# PCB-CMB-5-ETHERMEGA.net
KiCad netlist of a schematic drawn in EAGLE
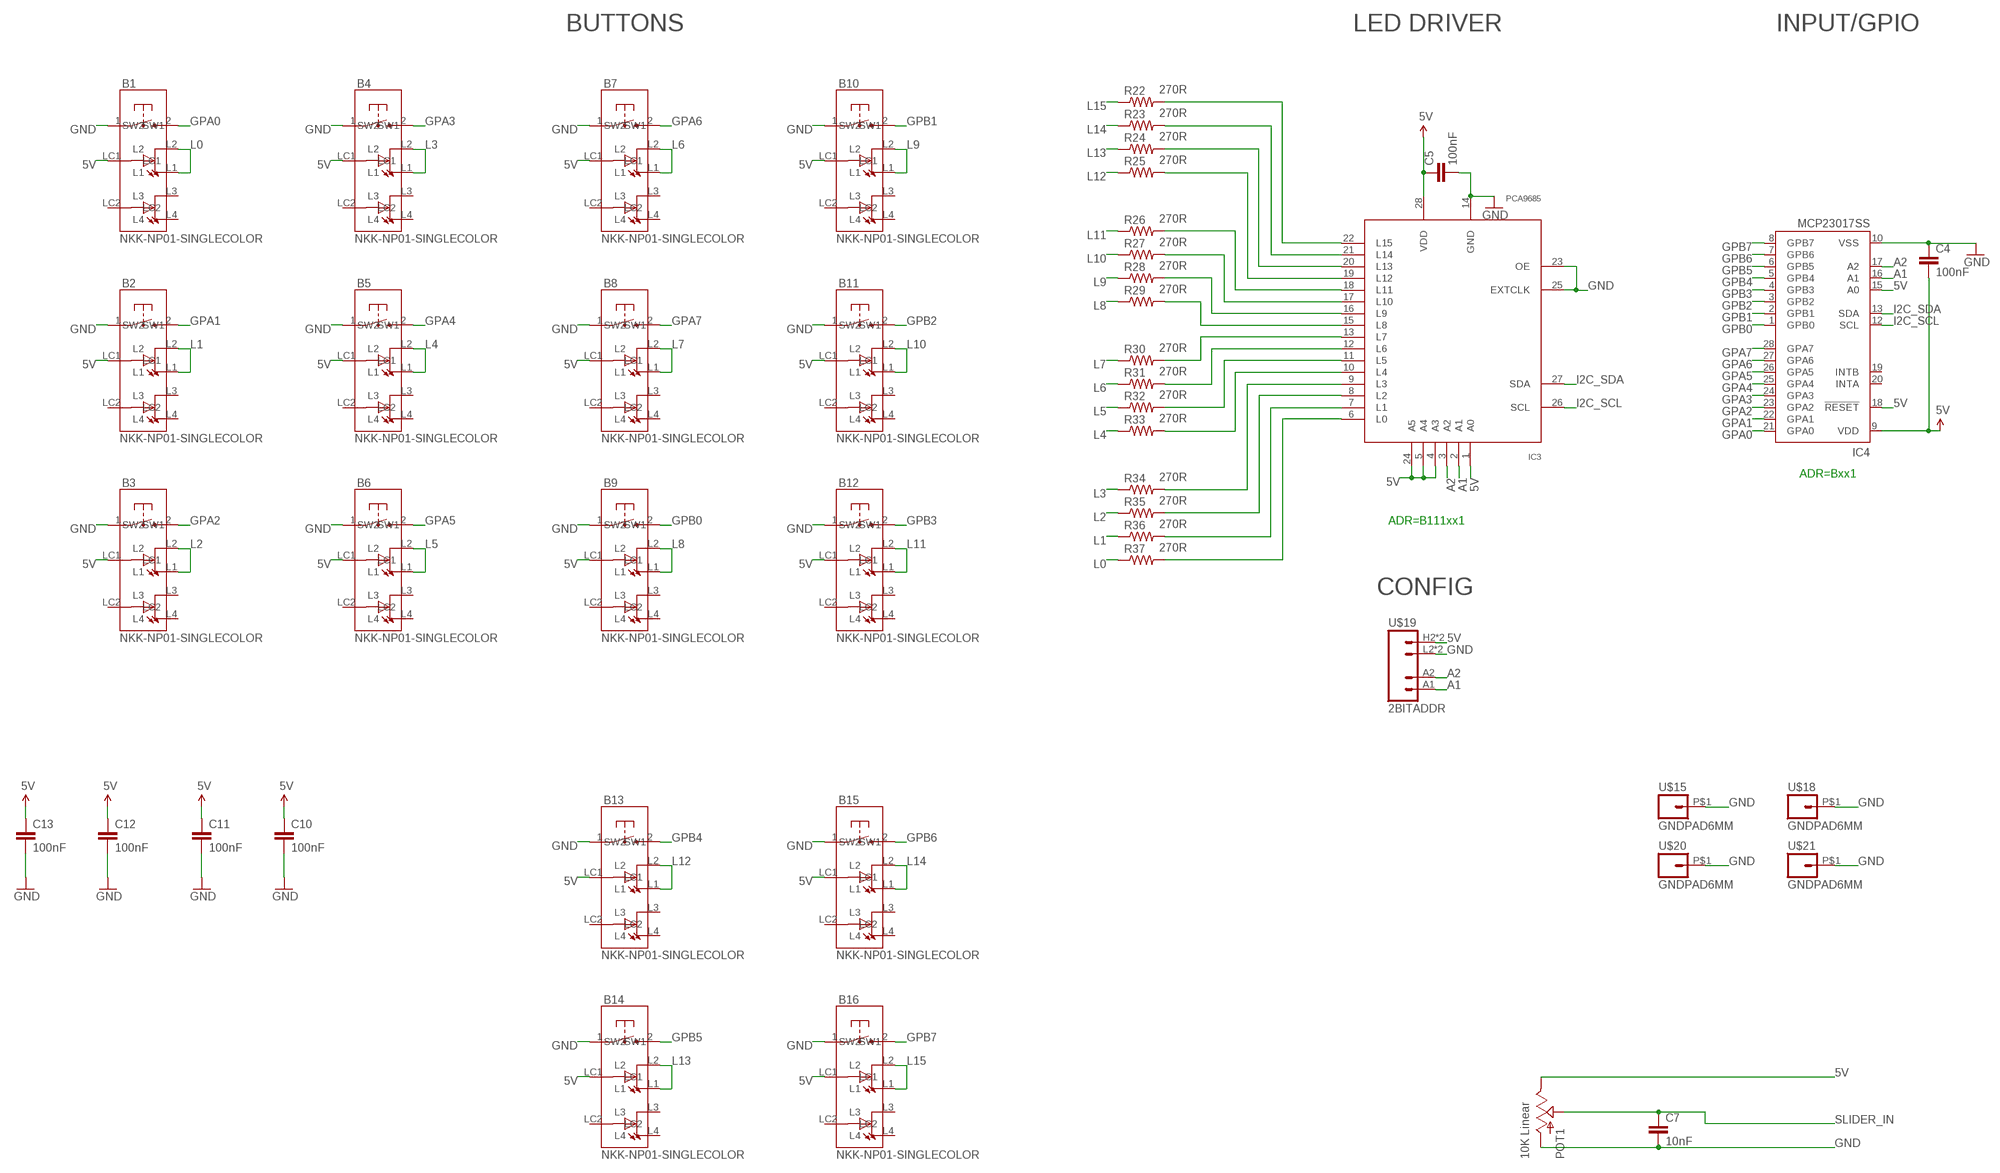
[diagram p0: schematic, sheet 1, part 1 of 2]
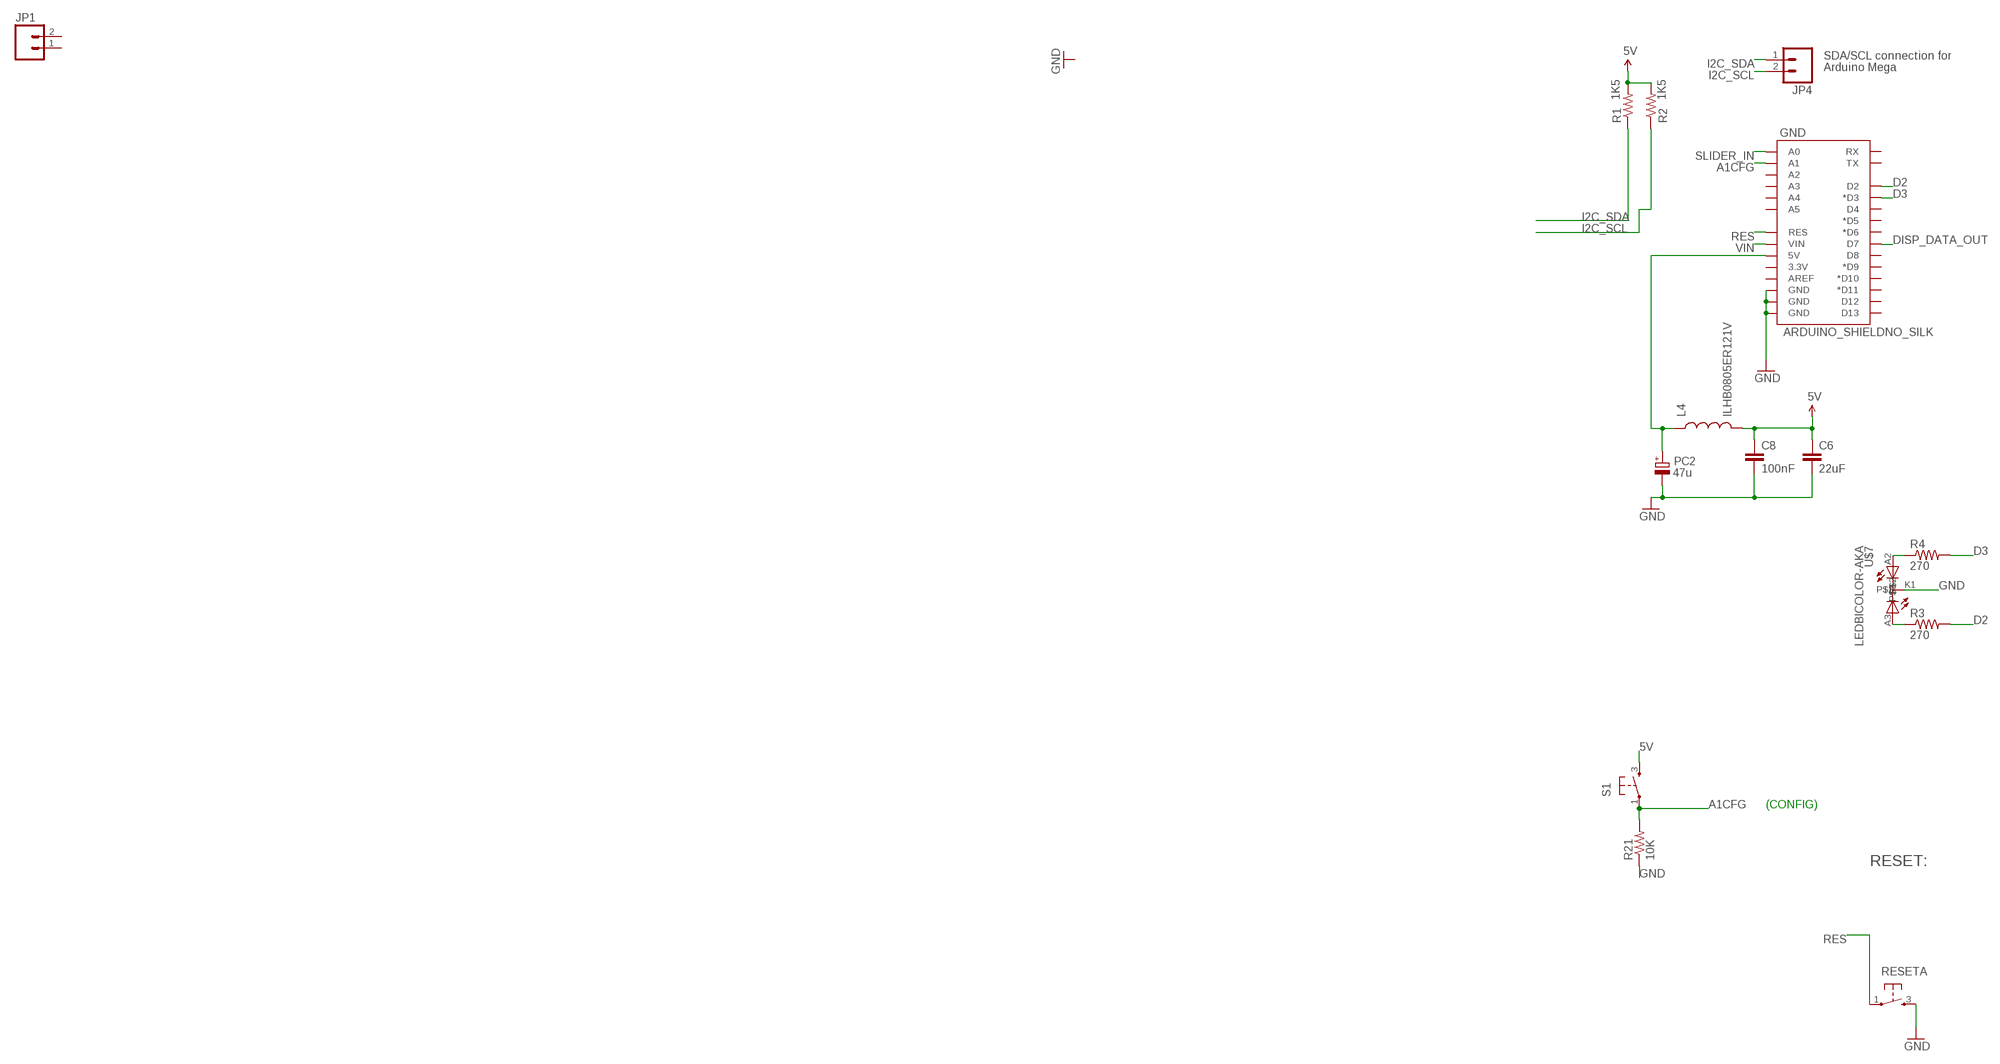
[diagram p1: schematic, sheet 1, part 2 of 2]

(export (version "E")
  (design (tool "Eeschema 10.0.6"))
  (components
    (comp (ref "B1")
      (value "NKK-NP01-SINGLECOLOR")
      (footprint "eagle-import:NKK-NP01")
      (libsource (lib "eagle-import") (part "NKK-NP01-SINGLECOLOR"))
    )
    (comp (ref "B2")
      (value "NKK-NP01-SINGLECOLOR")
      (footprint "eagle-import:NKK-NP01")
      (libsource (lib "eagle-import") (part "NKK-NP01-SINGLECOLOR"))
    )
    (comp (ref "B3")
      (value "NKK-NP01-SINGLECOLOR")
      (footprint "eagle-import:NKK-NP01")
      (libsource (lib "eagle-import") (part "NKK-NP01-SINGLECOLOR"))
    )
    (comp (ref "B4")
      (value "NKK-NP01-SINGLECOLOR")
      (footprint "eagle-import:NKK-NP01")
      (libsource (lib "eagle-import") (part "NKK-NP01-SINGLECOLOR"))
    )
    (comp (ref "B5")
      (value "NKK-NP01-SINGLECOLOR")
      (footprint "eagle-import:NKK-NP01")
      (libsource (lib "eagle-import") (part "NKK-NP01-SINGLECOLOR"))
    )
    (comp (ref "B6")
      (value "NKK-NP01-SINGLECOLOR")
      (footprint "eagle-import:NKK-NP01")
      (libsource (lib "eagle-import") (part "NKK-NP01-SINGLECOLOR"))
    )
    (comp (ref "B7")
      (value "NKK-NP01-SINGLECOLOR")
      (footprint "eagle-import:NKK-NP01")
      (libsource (lib "eagle-import") (part "NKK-NP01-SINGLECOLOR"))
    )
    (comp (ref "B8")
      (value "NKK-NP01-SINGLECOLOR")
      (footprint "eagle-import:NKK-NP01")
      (libsource (lib "eagle-import") (part "NKK-NP01-SINGLECOLOR"))
    )
    (comp (ref "B9")
      (value "NKK-NP01-SINGLECOLOR")
      (footprint "eagle-import:NKK-NP01")
      (libsource (lib "eagle-import") (part "NKK-NP01-SINGLECOLOR"))
    )
    (comp (ref "B10")
      (value "NKK-NP01-SINGLECOLOR")
      (footprint "eagle-import:NKK-NP01")
      (libsource (lib "eagle-import") (part "NKK-NP01-SINGLECOLOR"))
    )
    (comp (ref "B11")
      (value "NKK-NP01-SINGLECOLOR")
      (footprint "eagle-import:NKK-NP01")
      (libsource (lib "eagle-import") (part "NKK-NP01-SINGLECOLOR"))
    )
    (comp (ref "B12")
      (value "NKK-NP01-SINGLECOLOR")
      (footprint "eagle-import:NKK-NP01")
      (libsource (lib "eagle-import") (part "NKK-NP01-SINGLECOLOR"))
    )
    (comp (ref "B13")
      (value "NKK-NP01-SINGLECOLOR")
      (footprint "eagle-import:NKK-NP01")
      (libsource (lib "eagle-import") (part "NKK-NP01-SINGLECOLOR"))
    )
    (comp (ref "B14")
      (value "NKK-NP01-SINGLECOLOR")
      (footprint "eagle-import:NKK-NP01")
      (libsource (lib "eagle-import") (part "NKK-NP01-SINGLECOLOR"))
    )
    (comp (ref "B15")
      (value "NKK-NP01-SINGLECOLOR")
      (footprint "eagle-import:NKK-NP01")
      (libsource (lib "eagle-import") (part "NKK-NP01-SINGLECOLOR"))
    )
    (comp (ref "B16")
      (value "NKK-NP01-SINGLECOLOR")
      (footprint "eagle-import:NKK-NP01")
      (libsource (lib "eagle-import") (part "NKK-NP01-SINGLECOLOR"))
    )
    (comp (ref "C4")
      (value "100nF")
      (footprint "eagle-import:0603-CAP")
      (libsource (lib "eagle-import") (part "CAP0603-CAP"))
    )
    (comp (ref "C5")
      (value "100nF")
      (footprint "eagle-import:0603-CAP")
      (libsource (lib "eagle-import") (part "CAP0603-CAP"))
    )
    (comp (ref "C6")
      (value "22uF")
      (footprint "eagle-import:0805")
      (libsource (lib "eagle-import") (part "CAP0805"))
    )
    (comp (ref "C7")
      (value "10nF")
      (footprint "eagle-import:0603-CAP")
      (libsource (lib "eagle-import") (part "CAP0603-CAP"))
    )
    (comp (ref "C8")
      (value "100nF")
      (footprint "eagle-import:0603-CAP")
      (libsource (lib "eagle-import") (part "CAP0603-CAP"))
    )
    (comp (ref "C10")
      (value "100nF")
      (footprint "eagle-import:0603-CAP")
      (libsource (lib "eagle-import") (part "CAP0603-CAP"))
    )
    (comp (ref "C11")
      (value "100nF")
      (footprint "eagle-import:0603-CAP")
      (libsource (lib "eagle-import") (part "CAP0603-CAP"))
    )
    (comp (ref "C12")
      (value "100nF")
      (footprint "eagle-import:0603-CAP")
      (libsource (lib "eagle-import") (part "CAP0603-CAP"))
    )
    (comp (ref "C13")
      (value "100nF")
      (footprint "eagle-import:0603-CAP")
      (libsource (lib "eagle-import") (part "CAP0603-CAP"))
    )
    (comp (ref "GND")
      (value "ARDUINO_SHIELDNO_SILK")
      (footprint "eagle-import:DUEMILANOVE_VIAS")
      (libsource (lib "eagle-import") (part "ARDUINO_SHIELDNO_SILK"))
    )
    (comp (ref "IC3")
      (value "PCA9685")
      (footprint "eagle-import:TSSOP28")
      (libsource (lib "eagle-import") (part "PCA9685"))
    )
    (comp (ref "IC4")
      (value "MCP23017SS")
      (footprint "eagle-import:SSOP28")
      (fields
        (field (name "MF") "MICROCHIP")
        (field (name "MPN") "MCP23017-E/SS")
        (field (name "MPN_1") "MCP23017-E/SS")
        (field (name "OC_FARNELL") "1467674")
        (field (name "OC_NEWARK") "31K2960")
      )
      (libsource (lib "eagle-import") (part "MCP23017SS"))
    )
    (comp (ref "JP1")
      (value "M02PTH")
      (footprint "eagle-import:1X02")
      (libsource (lib "eagle-import") (part "M02PTH"))
    )
    (comp (ref "JP4")
      (value "M02PTH")
      (footprint "eagle-import:1X02")
      (libsource (lib "eagle-import") (part "M02PTH"))
    )
    (comp (ref "L4")
      (value "ILHB0805ER121V")
      (footprint "eagle-import:0805")
      (libsource (lib "eagle-import") (part "INDUCTOR0805"))
    )
    (comp (ref "PC2")
      (value "47u")
      (footprint "eagle-import:PANASONIC_D")
      (libsource (lib "eagle-import") (part "CPOL-EUD"))
    )
    (comp (ref "POT1")
      (value "10K Linear")
      (footprint "eagle-import:SLIDER20")
      (libsource (lib "eagle-import") (part "SLIDER20"))
    )
    (comp (ref "R1")
      (value "1K5")
      (footprint "eagle-import:0603-RES")
      (libsource (lib "eagle-import") (part "RESISTOR0603-RES"))
    )
    (comp (ref "R2")
      (value "1K5")
      (footprint "eagle-import:0603-RES")
      (libsource (lib "eagle-import") (part "RESISTOR0603-RES"))
    )
    (comp (ref "R3")
      (value "270")
      (footprint "eagle-import:0603-RES")
      (libsource (lib "eagle-import") (part "RESISTOR0603-RES"))
    )
    (comp (ref "R4")
      (value "270")
      (footprint "eagle-import:0603-RES")
      (libsource (lib "eagle-import") (part "RESISTOR0603-RES"))
    )
    (comp (ref "R21")
      (value "10K")
      (footprint "eagle-import:0603-RES")
      (libsource (lib "eagle-import") (part "RESISTOR0603-RES"))
    )
    (comp (ref "R22")
      (value "270R")
      (footprint "eagle-import:0603-RES")
      (libsource (lib "eagle-import") (part "RESISTOR0603-RES"))
    )
    (comp (ref "R23")
      (value "270R")
      (footprint "eagle-import:0603-RES")
      (libsource (lib "eagle-import") (part "RESISTOR0603-RES"))
    )
    (comp (ref "R24")
      (value "270R")
      (footprint "eagle-import:0603-RES")
      (libsource (lib "eagle-import") (part "RESISTOR0603-RES"))
    )
    (comp (ref "R25")
      (value "270R")
      (footprint "eagle-import:0603-RES")
      (libsource (lib "eagle-import") (part "RESISTOR0603-RES"))
    )
    (comp (ref "R26")
      (value "270R")
      (footprint "eagle-import:0603-RES")
      (libsource (lib "eagle-import") (part "RESISTOR0603-RES"))
    )
    (comp (ref "R27")
      (value "270R")
      (footprint "eagle-import:0603-RES")
      (libsource (lib "eagle-import") (part "RESISTOR0603-RES"))
    )
    (comp (ref "R28")
      (value "270R")
      (footprint "eagle-import:0603-RES")
      (libsource (lib "eagle-import") (part "RESISTOR0603-RES"))
    )
    (comp (ref "R29")
      (value "270R")
      (footprint "eagle-import:0603-RES")
      (libsource (lib "eagle-import") (part "RESISTOR0603-RES"))
    )
    (comp (ref "R30")
      (value "270R")
      (footprint "eagle-import:0603-RES")
      (libsource (lib "eagle-import") (part "RESISTOR0603-RES"))
    )
    (comp (ref "R31")
      (value "270R")
      (footprint "eagle-import:0603-RES")
      (libsource (lib "eagle-import") (part "RESISTOR0603-RES"))
    )
    (comp (ref "R32")
      (value "270R")
      (footprint "eagle-import:0603-RES")
      (libsource (lib "eagle-import") (part "RESISTOR0603-RES"))
    )
    (comp (ref "R33")
      (value "270R")
      (footprint "eagle-import:0603-RES")
      (libsource (lib "eagle-import") (part "RESISTOR0603-RES"))
    )
    (comp (ref "R34")
      (value "270R")
      (footprint "eagle-import:0603-RES")
      (libsource (lib "eagle-import") (part "RESISTOR0603-RES"))
    )
    (comp (ref "R35")
      (value "270R")
      (footprint "eagle-import:0603-RES")
      (libsource (lib "eagle-import") (part "RESISTOR0603-RES"))
    )
    (comp (ref "R36")
      (value "270R")
      (footprint "eagle-import:0603-RES")
      (libsource (lib "eagle-import") (part "RESISTOR0603-RES"))
    )
    (comp (ref "R37")
      (value "270R")
      (footprint "eagle-import:0603-RES")
      (libsource (lib "eagle-import") (part "RESISTOR0603-RES"))
    )
    (comp (ref "RESETA")
      (value "TAC_SWITCH")
      (footprint "eagle-import:PUSHBUTTON")
      (libsource (lib "eagle-import") (part "TAC_SWITCH"))
    )
    (comp (ref "S1")
      (value "TAC_SWITCH")
      (footprint "eagle-import:PUSHBUTTON")
      (libsource (lib "eagle-import") (part "TAC_SWITCH"))
    )
    (comp (ref "U$7")
      (value "LEDBICOLOR-AKA")
      (footprint "eagle-import:LED5MM-BICOLOR")
      (libsource (lib "eagle-import") (part "LEDBICOLOR-AKA"))
    )
    (comp (ref "U$15")
      (value "GNDPAD6MM")
      (footprint "eagle-import:3.2MMPAD6MM")
      (libsource (lib "eagle-import") (part "GNDPAD6MM"))
    )
    (comp (ref "U$18")
      (value "GNDPAD6MM")
      (footprint "eagle-import:3.2MMPAD6MM")
      (libsource (lib "eagle-import") (part "GNDPAD6MM"))
    )
    (comp (ref "U$19")
      (value "2BITADDR")
      (footprint "eagle-import:2BITADDR")
      (libsource (lib "eagle-import") (part "2BITADDR"))
    )
    (comp (ref "U$20")
      (value "GNDPAD6MM")
      (footprint "eagle-import:3.2MMPAD6MM")
      (libsource (lib "eagle-import") (part "GNDPAD6MM"))
    )
    (comp (ref "U$21")
      (value "GNDPAD6MM")
      (footprint "eagle-import:3.2MMPAD6MM")
      (libsource (lib "eagle-import") (part "GNDPAD6MM"))
    )
  )
  (nets
    (net (code "1") (name "5V") (class "Default")
      (node (ref "B1") (pin "LC1") (pinfunction "LC1_LC1") (pintype "bidirectional"))
      (node (ref "B10") (pin "LC1") (pinfunction "LC1_LC1") (pintype "bidirectional"))
      (node (ref "B11") (pin "LC1") (pinfunction "LC1_LC1") (pintype "bidirectional"))
      (node (ref "B12") (pin "LC1") (pinfunction "LC1_LC1") (pintype "bidirectional"))
      (node (ref "B13") (pin "LC1") (pinfunction "LC1_LC1") (pintype "bidirectional"))
      (node (ref "B14") (pin "LC1") (pinfunction "LC1_LC1") (pintype "bidirectional"))
      (node (ref "B15") (pin "LC1") (pinfunction "LC1_LC1") (pintype "bidirectional"))
      (node (ref "B16") (pin "LC1") (pinfunction "LC1_LC1") (pintype "bidirectional"))
      (node (ref "B2") (pin "LC1") (pinfunction "LC1_LC1") (pintype "bidirectional"))
      (node (ref "B3") (pin "LC1") (pinfunction "LC1_LC1") (pintype "bidirectional"))
      (node (ref "B4") (pin "LC1") (pinfunction "LC1_LC1") (pintype "bidirectional"))
      (node (ref "B5") (pin "LC1") (pinfunction "LC1_LC1") (pintype "bidirectional"))
      (node (ref "B6") (pin "LC1") (pinfunction "LC1_LC1") (pintype "bidirectional"))
      (node (ref "B7") (pin "LC1") (pinfunction "LC1_LC1") (pintype "bidirectional"))
      (node (ref "B8") (pin "LC1") (pinfunction "LC1_LC1") (pintype "bidirectional"))
      (node (ref "B9") (pin "LC1") (pinfunction "LC1_LC1") (pintype "bidirectional"))
      (node (ref "C10") (pin "1") (pinfunction "1_1") (pintype "passive"))
      (node (ref "C11") (pin "1") (pinfunction "1_1") (pintype "passive"))
      (node (ref "C12") (pin "1") (pinfunction "1_1") (pintype "passive"))
      (node (ref "C13") (pin "1") (pinfunction "1_1") (pintype "passive"))
      (node (ref "C4") (pin "2") (pinfunction "2_2") (pintype "passive"))
      (node (ref "C5") (pin "1") (pinfunction "1_1") (pintype "passive"))
      (node (ref "C6") (pin "1") (pinfunction "1_1") (pintype "passive"))
      (node (ref "C8") (pin "1") (pinfunction "1_1") (pintype "passive"))
      (node (ref "IC3") (pin "1") (pinfunction "A0_1") (pintype "input"))
      (node (ref "IC3") (pin "24") (pinfunction "A5_24") (pintype "input"))
      (node (ref "IC3") (pin "28") (pinfunction "VDD_28") (pintype "power_in"))
      (node (ref "IC3") (pin "4") (pinfunction "A3_4") (pintype "input"))
      (node (ref "IC3") (pin "5") (pinfunction "A4_5") (pintype "input"))
      (node (ref "IC4") (pin "15") (pinfunction "A0_15") (pintype "input"))
      (node (ref "IC4") (pin "18") (pinfunction "~{RESET}_18") (pintype "input"))
      (node (ref "IC4") (pin "9") (pinfunction "VDD_9") (pintype "power_in"))
      (node (ref "L4") (pin "2") (pinfunction "2_2") (pintype "passive"))
      (node (ref "POT1") (pin "1") (pinfunction "E_1") (pintype "passive"))
      (node (ref "R1") (pin "2") (pinfunction "2_2") (pintype "passive"))
      (node (ref "R2") (pin "2") (pinfunction "2_2") (pintype "passive"))
      (node (ref "S1") (pin "3") (pinfunction "3_3") (pintype "passive"))
      (node (ref "U$19") (pin "H2") (pinfunction "VCC_H2") (pintype "passive"))
      (node (ref "U$19") (pin "H3") (pinfunction "VCC_H3") (pintype "passive"))
    )
    (net (code "2") (name "A1") (class "Default")
      (node (ref "IC3") (pin "2") (pinfunction "A1_2") (pintype "input"))
      (node (ref "IC4") (pin "16") (pinfunction "A1_16") (pintype "input"))
      (node (ref "U$19") (pin "A1") (pinfunction "A1_A1") (pintype "passive"))
    )
    (net (code "3") (name "A1CFG") (class "Default")
      (node (ref "GND") (pin "A1") (pinfunction "A1_A1") (pintype "bidirectional"))
      (node (ref "R21") (pin "2") (pinfunction "2_2") (pintype "passive"))
      (node (ref "S1") (pin "1") (pinfunction "1_1") (pintype "passive"))
    )
    (net (code "4") (name "A2") (class "Default")
      (node (ref "IC3") (pin "3") (pinfunction "A2_3") (pintype "input"))
      (node (ref "IC4") (pin "17") (pinfunction "A2_17") (pintype "input"))
      (node (ref "U$19") (pin "A2") (pinfunction "A2_A2") (pintype "passive"))
    )
    (net (code "5") (name "D2") (class "Default")
      (node (ref "GND") (pin "D2") (pinfunction "D2_D2") (pintype "bidirectional"))
      (node (ref "R3") (pin "2") (pinfunction "2_2") (pintype "passive"))
    )
    (net (code "6") (name "D3") (class "Default")
      (node (ref "GND") (pin "D3") (pinfunction "*D3_D3") (pintype "bidirectional"))
      (node (ref "R4") (pin "2") (pinfunction "2_2") (pintype "passive"))
    )
    (net (code "7") (name "DISP_DATA_OUT") (class "Default")
      (node (ref "GND") (pin "D7") (pinfunction "D7_D7") (pintype "bidirectional"))
    )
    (net (code "8") (name "GND") (class "Default")
      (node (ref "B1") (pin "1") (pinfunction "SW1_1") (pintype "bidirectional"))
      (node (ref "B10") (pin "1") (pinfunction "SW1_1") (pintype "bidirectional"))
      (node (ref "B11") (pin "1") (pinfunction "SW1_1") (pintype "bidirectional"))
      (node (ref "B12") (pin "1") (pinfunction "SW1_1") (pintype "bidirectional"))
      (node (ref "B13") (pin "1") (pinfunction "SW1_1") (pintype "bidirectional"))
      (node (ref "B14") (pin "1") (pinfunction "SW1_1") (pintype "bidirectional"))
      (node (ref "B15") (pin "1") (pinfunction "SW1_1") (pintype "bidirectional"))
      (node (ref "B16") (pin "1") (pinfunction "SW1_1") (pintype "bidirectional"))
      (node (ref "B2") (pin "1") (pinfunction "SW1_1") (pintype "bidirectional"))
      (node (ref "B3") (pin "1") (pinfunction "SW1_1") (pintype "bidirectional"))
      (node (ref "B4") (pin "1") (pinfunction "SW1_1") (pintype "bidirectional"))
      (node (ref "B5") (pin "1") (pinfunction "SW1_1") (pintype "bidirectional"))
      (node (ref "B6") (pin "1") (pinfunction "SW1_1") (pintype "bidirectional"))
      (node (ref "B7") (pin "1") (pinfunction "SW1_1") (pintype "bidirectional"))
      (node (ref "B8") (pin "1") (pinfunction "SW1_1") (pintype "bidirectional"))
      (node (ref "B9") (pin "1") (pinfunction "SW1_1") (pintype "bidirectional"))
      (node (ref "C10") (pin "2") (pinfunction "2_2") (pintype "passive"))
      (node (ref "C11") (pin "2") (pinfunction "2_2") (pintype "passive"))
      (node (ref "C12") (pin "2") (pinfunction "2_2") (pintype "passive"))
      (node (ref "C13") (pin "2") (pinfunction "2_2") (pintype "passive"))
      (node (ref "C4") (pin "1") (pinfunction "1_1") (pintype "passive"))
      (node (ref "C5") (pin "2") (pinfunction "2_2") (pintype "passive"))
      (node (ref "C6") (pin "2") (pinfunction "2_2") (pintype "passive"))
      (node (ref "C7") (pin "2") (pinfunction "2_2") (pintype "passive"))
      (node (ref "C8") (pin "2") (pinfunction "2_2") (pintype "passive"))
      (node (ref "GND") (pin "GND@0") (pinfunction "GND_GND@0") (pintype "bidirectional"))
      (node (ref "GND") (pin "GND@1") (pinfunction "GND_GND@1") (pintype "bidirectional"))
      (node (ref "GND") (pin "GND@2") (pinfunction "GND_GND@2") (pintype "bidirectional"))
      (node (ref "IC3") (pin "14") (pinfunction "GND_14") (pintype "power_in"))
      (node (ref "IC3") (pin "23") (pinfunction "OE_23") (pintype "input"))
      (node (ref "IC3") (pin "25") (pinfunction "EXTCLK_25") (pintype "input"))
      (node (ref "IC4") (pin "10") (pinfunction "VSS_10") (pintype "power_in"))
      (node (ref "PC2") (pin "-") (pinfunction "-_-") (pintype "passive"))
      (node (ref "POT1") (pin "3") (pinfunction "A_3") (pintype "passive"))
      (node (ref "R21") (pin "1") (pinfunction "1_1") (pintype "passive"))
      (node (ref "RESETA") (pin "3") (pinfunction "3_3") (pintype "passive"))
      (node (ref "U$15") (pin "P$1") (pinfunction "1_P$1") (pintype "passive"))
      (node (ref "U$18") (pin "P$1") (pinfunction "1_P$1") (pintype "passive"))
      (node (ref "U$19") (pin "L2") (pinfunction "GND_L2") (pintype "passive"))
      (node (ref "U$19") (pin "L3") (pinfunction "GND_L3") (pintype "passive"))
      (node (ref "U$20") (pin "P$1") (pinfunction "1_P$1") (pintype "passive"))
      (node (ref "U$21") (pin "P$1") (pinfunction "1_P$1") (pintype "passive"))
      (node (ref "U$7") (pin "K1") (pinfunction "P$1_K1") (pintype "bidirectional"))
    )
    (net (code "9") (name "GPA0") (class "Default")
      (node (ref "B1") (pin "2") (pinfunction "SW2_2") (pintype "bidirectional"))
      (node (ref "IC4") (pin "21") (pinfunction "GPA0_21") (pintype "bidirectional"))
    )
    (net (code "10") (name "GPA1") (class "Default")
      (node (ref "B2") (pin "2") (pinfunction "SW2_2") (pintype "bidirectional"))
      (node (ref "IC4") (pin "22") (pinfunction "GPA1_22") (pintype "bidirectional"))
    )
    (net (code "11") (name "GPA2") (class "Default")
      (node (ref "B3") (pin "2") (pinfunction "SW2_2") (pintype "bidirectional"))
      (node (ref "IC4") (pin "23") (pinfunction "GPA2_23") (pintype "bidirectional"))
    )
    (net (code "12") (name "GPA3") (class "Default")
      (node (ref "B4") (pin "2") (pinfunction "SW2_2") (pintype "bidirectional"))
      (node (ref "IC4") (pin "24") (pinfunction "GPA3_24") (pintype "bidirectional"))
    )
    (net (code "13") (name "GPA4") (class "Default")
      (node (ref "B5") (pin "2") (pinfunction "SW2_2") (pintype "bidirectional"))
      (node (ref "IC4") (pin "25") (pinfunction "GPA4_25") (pintype "bidirectional"))
    )
    (net (code "14") (name "GPA5") (class "Default")
      (node (ref "B6") (pin "2") (pinfunction "SW2_2") (pintype "bidirectional"))
      (node (ref "IC4") (pin "26") (pinfunction "GPA5_26") (pintype "bidirectional"))
    )
    (net (code "15") (name "GPA6") (class "Default")
      (node (ref "B7") (pin "2") (pinfunction "SW2_2") (pintype "bidirectional"))
      (node (ref "IC4") (pin "27") (pinfunction "GPA6_27") (pintype "bidirectional"))
    )
    (net (code "16") (name "GPA7") (class "Default")
      (node (ref "B8") (pin "2") (pinfunction "SW2_2") (pintype "bidirectional"))
      (node (ref "IC4") (pin "28") (pinfunction "GPA7_28") (pintype "bidirectional"))
    )
    (net (code "17") (name "GPB0") (class "Default")
      (node (ref "B9") (pin "2") (pinfunction "SW2_2") (pintype "bidirectional"))
      (node (ref "IC4") (pin "1") (pinfunction "GPB0_1") (pintype "bidirectional"))
    )
    (net (code "18") (name "GPB1") (class "Default")
      (node (ref "B10") (pin "2") (pinfunction "SW2_2") (pintype "bidirectional"))
      (node (ref "IC4") (pin "2") (pinfunction "GPB1_2") (pintype "bidirectional"))
    )
    (net (code "19") (name "GPB2") (class "Default")
      (node (ref "B11") (pin "2") (pinfunction "SW2_2") (pintype "bidirectional"))
      (node (ref "IC4") (pin "3") (pinfunction "GPB2_3") (pintype "bidirectional"))
    )
    (net (code "20") (name "GPB3") (class "Default")
      (node (ref "B12") (pin "2") (pinfunction "SW2_2") (pintype "bidirectional"))
      (node (ref "IC4") (pin "4") (pinfunction "GPB3_4") (pintype "bidirectional"))
    )
    (net (code "21") (name "GPB4") (class "Default")
      (node (ref "B13") (pin "2") (pinfunction "SW2_2") (pintype "bidirectional"))
      (node (ref "IC4") (pin "5") (pinfunction "GPB4_5") (pintype "bidirectional"))
    )
    (net (code "22") (name "GPB5") (class "Default")
      (node (ref "B14") (pin "2") (pinfunction "SW2_2") (pintype "bidirectional"))
      (node (ref "IC4") (pin "6") (pinfunction "GPB5_6") (pintype "bidirectional"))
    )
    (net (code "23") (name "GPB6") (class "Default")
      (node (ref "B15") (pin "2") (pinfunction "SW2_2") (pintype "bidirectional"))
      (node (ref "IC4") (pin "7") (pinfunction "GPB6_7") (pintype "bidirectional"))
    )
    (net (code "24") (name "GPB7") (class "Default")
      (node (ref "B16") (pin "2") (pinfunction "SW2_2") (pintype "bidirectional"))
      (node (ref "IC4") (pin "8") (pinfunction "GPB7_8") (pintype "bidirectional"))
    )
    (net (code "25") (name "I2C_SCL") (class "Default")
      (node (ref "IC3") (pin "26") (pinfunction "SCL_26") (pintype "input"))
      (node (ref "IC4") (pin "12") (pinfunction "SCL_12") (pintype "input"))
      (node (ref "JP4") (pin "2") (pinfunction "2_2") (pintype "passive"))
      (node (ref "R2") (pin "1") (pinfunction "1_1") (pintype "passive"))
    )
    (net (code "26") (name "I2C_SDA") (class "Default")
      (node (ref "IC3") (pin "27") (pinfunction "SDA_27") (pintype "input"))
      (node (ref "IC4") (pin "13") (pinfunction "SDA_13") (pintype "bidirectional"))
      (node (ref "JP4") (pin "1") (pinfunction "1_1") (pintype "passive"))
      (node (ref "R1") (pin "1") (pinfunction "1_1") (pintype "passive"))
    )
    (net (code "27") (name "L0") (class "Default")
      (node (ref "B1") (pin "L1") (pinfunction "L1_L1") (pintype "bidirectional"))
      (node (ref "B1") (pin "L2") (pinfunction "L2_L2") (pintype "bidirectional"))
      (node (ref "R37") (pin "1") (pinfunction "1_1") (pintype "passive"))
    )
    (net (code "28") (name "L1") (class "Default")
      (node (ref "B2") (pin "L1") (pinfunction "L1_L1") (pintype "bidirectional"))
      (node (ref "B2") (pin "L2") (pinfunction "L2_L2") (pintype "bidirectional"))
      (node (ref "R36") (pin "1") (pinfunction "1_1") (pintype "passive"))
    )
    (net (code "29") (name "L2") (class "Default")
      (node (ref "B3") (pin "L1") (pinfunction "L1_L1") (pintype "bidirectional"))
      (node (ref "B3") (pin "L2") (pinfunction "L2_L2") (pintype "bidirectional"))
      (node (ref "R35") (pin "1") (pinfunction "1_1") (pintype "passive"))
    )
    (net (code "30") (name "L3") (class "Default")
      (node (ref "B4") (pin "L1") (pinfunction "L1_L1") (pintype "bidirectional"))
      (node (ref "B4") (pin "L2") (pinfunction "L2_L2") (pintype "bidirectional"))
      (node (ref "R34") (pin "1") (pinfunction "1_1") (pintype "passive"))
    )
    (net (code "31") (name "L4") (class "Default")
      (node (ref "B5") (pin "L1") (pinfunction "L1_L1") (pintype "bidirectional"))
      (node (ref "B5") (pin "L2") (pinfunction "L2_L2") (pintype "bidirectional"))
      (node (ref "R33") (pin "1") (pinfunction "1_1") (pintype "passive"))
    )
    (net (code "32") (name "L5") (class "Default")
      (node (ref "B6") (pin "L1") (pinfunction "L1_L1") (pintype "bidirectional"))
      (node (ref "B6") (pin "L2") (pinfunction "L2_L2") (pintype "bidirectional"))
      (node (ref "R32") (pin "1") (pinfunction "1_1") (pintype "passive"))
    )
    (net (code "33") (name "L6") (class "Default")
      (node (ref "B7") (pin "L1") (pinfunction "L1_L1") (pintype "bidirectional"))
      (node (ref "B7") (pin "L2") (pinfunction "L2_L2") (pintype "bidirectional"))
      (node (ref "R31") (pin "1") (pinfunction "1_1") (pintype "passive"))
    )
    (net (code "34") (name "L7") (class "Default")
      (node (ref "B8") (pin "L1") (pinfunction "L1_L1") (pintype "bidirectional"))
      (node (ref "B8") (pin "L2") (pinfunction "L2_L2") (pintype "bidirectional"))
      (node (ref "R30") (pin "1") (pinfunction "1_1") (pintype "passive"))
    )
    (net (code "35") (name "L8") (class "Default")
      (node (ref "B9") (pin "L1") (pinfunction "L1_L1") (pintype "bidirectional"))
      (node (ref "B9") (pin "L2") (pinfunction "L2_L2") (pintype "bidirectional"))
      (node (ref "R29") (pin "1") (pinfunction "1_1") (pintype "passive"))
    )
    (net (code "36") (name "L9") (class "Default")
      (node (ref "B10") (pin "L1") (pinfunction "L1_L1") (pintype "bidirectional"))
      (node (ref "B10") (pin "L2") (pinfunction "L2_L2") (pintype "bidirectional"))
      (node (ref "R28") (pin "1") (pinfunction "1_1") (pintype "passive"))
    )
    (net (code "37") (name "L10") (class "Default")
      (node (ref "B11") (pin "L1") (pinfunction "L1_L1") (pintype "bidirectional"))
      (node (ref "B11") (pin "L2") (pinfunction "L2_L2") (pintype "bidirectional"))
      (node (ref "R27") (pin "1") (pinfunction "1_1") (pintype "passive"))
    )
    (net (code "38") (name "L11") (class "Default")
      (node (ref "B12") (pin "L1") (pinfunction "L1_L1") (pintype "bidirectional"))
      (node (ref "B12") (pin "L2") (pinfunction "L2_L2") (pintype "bidirectional"))
      (node (ref "R26") (pin "1") (pinfunction "1_1") (pintype "passive"))
    )
    (net (code "39") (name "L12") (class "Default")
      (node (ref "B13") (pin "L1") (pinfunction "L1_L1") (pintype "bidirectional"))
      (node (ref "B13") (pin "L2") (pinfunction "L2_L2") (pintype "bidirectional"))
      (node (ref "R25") (pin "1") (pinfunction "1_1") (pintype "passive"))
    )
    (net (code "40") (name "L13") (class "Default")
      (node (ref "B14") (pin "L1") (pinfunction "L1_L1") (pintype "bidirectional"))
      (node (ref "B14") (pin "L2") (pinfunction "L2_L2") (pintype "bidirectional"))
      (node (ref "R24") (pin "1") (pinfunction "1_1") (pintype "passive"))
    )
    (net (code "41") (name "L14") (class "Default")
      (node (ref "B15") (pin "L1") (pinfunction "L1_L1") (pintype "bidirectional"))
      (node (ref "B15") (pin "L2") (pinfunction "L2_L2") (pintype "bidirectional"))
      (node (ref "R23") (pin "1") (pinfunction "1_1") (pintype "passive"))
    )
    (net (code "42") (name "L15") (class "Default")
      (node (ref "B16") (pin "L1") (pinfunction "L1_L1") (pintype "bidirectional"))
      (node (ref "B16") (pin "L2") (pinfunction "L2_L2") (pintype "bidirectional"))
      (node (ref "R22") (pin "1") (pinfunction "1_1") (pintype "passive"))
    )
    (net (code "43") (name "Net-(GND-Pad5V)") (class "Default")
      (node (ref "GND") (pin "5V") (pinfunction "5V_5V") (pintype "bidirectional"))
      (node (ref "L4") (pin "1") (pinfunction "1_1") (pintype "passive"))
      (node (ref "PC2") (pin "+") (pinfunction "+_+") (pintype "passive"))
    )
    (net (code "44") (name "Net-(IC3-L0)") (class "Default")
      (node (ref "IC3") (pin "6") (pinfunction "L0_6") (pintype "output"))
      (node (ref "R37") (pin "2") (pinfunction "2_2") (pintype "passive"))
    )
    (net (code "45") (name "Net-(IC3-L1)") (class "Default")
      (node (ref "IC3") (pin "7") (pinfunction "L1_7") (pintype "output"))
      (node (ref "R36") (pin "2") (pinfunction "2_2") (pintype "passive"))
    )
    (net (code "46") (name "Net-(IC3-L2)") (class "Default")
      (node (ref "IC3") (pin "8") (pinfunction "L2_8") (pintype "output"))
      (node (ref "R35") (pin "2") (pinfunction "2_2") (pintype "passive"))
    )
    (net (code "47") (name "Net-(IC3-L3)") (class "Default")
      (node (ref "IC3") (pin "9") (pinfunction "L3_9") (pintype "output"))
      (node (ref "R34") (pin "2") (pinfunction "2_2") (pintype "passive"))
    )
    (net (code "48") (name "Net-(IC3-L4)") (class "Default")
      (node (ref "IC3") (pin "10") (pinfunction "L4_10") (pintype "output"))
      (node (ref "R33") (pin "2") (pinfunction "2_2") (pintype "passive"))
    )
    (net (code "49") (name "Net-(IC3-L5)") (class "Default")
      (node (ref "IC3") (pin "11") (pinfunction "L5_11") (pintype "output"))
      (node (ref "R32") (pin "2") (pinfunction "2_2") (pintype "passive"))
    )
    (net (code "50") (name "Net-(IC3-L6)") (class "Default")
      (node (ref "IC3") (pin "12") (pinfunction "L6_12") (pintype "output"))
      (node (ref "R31") (pin "2") (pinfunction "2_2") (pintype "passive"))
    )
    (net (code "51") (name "Net-(IC3-L7)") (class "Default")
      (node (ref "IC3") (pin "13") (pinfunction "L7_13") (pintype "output"))
      (node (ref "R30") (pin "2") (pinfunction "2_2") (pintype "passive"))
    )
    (net (code "52") (name "Net-(IC3-L8)") (class "Default")
      (node (ref "IC3") (pin "15") (pinfunction "L8_15") (pintype "output"))
      (node (ref "R29") (pin "2") (pinfunction "2_2") (pintype "passive"))
    )
    (net (code "53") (name "Net-(IC3-L9)") (class "Default")
      (node (ref "IC3") (pin "16") (pinfunction "L9_16") (pintype "output"))
      (node (ref "R28") (pin "2") (pinfunction "2_2") (pintype "passive"))
    )
    (net (code "54") (name "Net-(IC3-L10)") (class "Default")
      (node (ref "IC3") (pin "17") (pinfunction "L10_17") (pintype "output"))
      (node (ref "R27") (pin "2") (pinfunction "2_2") (pintype "passive"))
    )
    (net (code "55") (name "Net-(IC3-L11)") (class "Default")
      (node (ref "IC3") (pin "18") (pinfunction "L11_18") (pintype "output"))
      (node (ref "R26") (pin "2") (pinfunction "2_2") (pintype "passive"))
    )
    (net (code "56") (name "Net-(IC3-L12)") (class "Default")
      (node (ref "IC3") (pin "19") (pinfunction "L12_19") (pintype "output"))
      (node (ref "R25") (pin "2") (pinfunction "2_2") (pintype "passive"))
    )
    (net (code "57") (name "Net-(IC3-L13)") (class "Default")
      (node (ref "IC3") (pin "20") (pinfunction "L13_20") (pintype "output"))
      (node (ref "R24") (pin "2") (pinfunction "2_2") (pintype "passive"))
    )
    (net (code "58") (name "Net-(IC3-L14)") (class "Default")
      (node (ref "IC3") (pin "21") (pinfunction "L14_21") (pintype "output"))
      (node (ref "R23") (pin "2") (pinfunction "2_2") (pintype "passive"))
    )
    (net (code "59") (name "Net-(IC3-L15)") (class "Default")
      (node (ref "IC3") (pin "22") (pinfunction "L15_22") (pintype "output"))
      (node (ref "R22") (pin "2") (pinfunction "2_2") (pintype "passive"))
    )
    (net (code "60") (name "Net-(U$7-P$2)") (class "Default")
      (node (ref "R4") (pin "1") (pinfunction "1_1") (pintype "passive"))
      (node (ref "U$7") (pin "A2") (pinfunction "P$2_A2") (pintype "bidirectional"))
    )
    (net (code "61") (name "Net-(U$7-P$3)") (class "Default")
      (node (ref "R3") (pin "1") (pinfunction "1_1") (pintype "passive"))
      (node (ref "U$7") (pin "A3") (pinfunction "P$3_A3") (pintype "bidirectional"))
    )
    (net (code "62") (name "RES") (class "Default")
      (node (ref "GND") (pin "RES") (pinfunction "RES_RES") (pintype "bidirectional"))
      (node (ref "RESETA") (pin "1") (pinfunction "1_1") (pintype "passive"))
    )
    (net (code "63") (name "SLIDER_IN") (class "Default")
      (node (ref "C7") (pin "1") (pinfunction "1_1") (pintype "passive"))
      (node (ref "GND") (pin "A0") (pinfunction "A0_A0") (pintype "bidirectional"))
      (node (ref "POT1") (pin "2A") (pinfunction "S_2A") (pintype "passive"))
    )
    (net (code "64") (name "VIN") (class "Default")
      (node (ref "GND") (pin "VIN") (pinfunction "VIN_VIN") (pintype "bidirectional"))
    )
    (net (code "65") (name "unconnected-(B1-PadL3)") (class "Default")
      (node (ref "B1") (pin "L3") (pinfunction "L3_L3") (pintype "bidirectional"))
    )
    (net (code "66") (name "unconnected-(B1-PadL4)") (class "Default")
      (node (ref "B1") (pin "L4") (pinfunction "L4_L4") (pintype "bidirectional"))
    )
    (net (code "67") (name "unconnected-(B1-PadLC2)") (class "Default")
      (node (ref "B1") (pin "LC2") (pinfunction "LC2_LC2") (pintype "bidirectional"))
    )
    (net (code "68") (name "unconnected-(B2-PadL3)") (class "Default")
      (node (ref "B2") (pin "L3") (pinfunction "L3_L3") (pintype "bidirectional"))
    )
    (net (code "69") (name "unconnected-(B2-PadL4)") (class "Default")
      (node (ref "B2") (pin "L4") (pinfunction "L4_L4") (pintype "bidirectional"))
    )
    (net (code "70") (name "unconnected-(B2-PadLC2)") (class "Default")
      (node (ref "B2") (pin "LC2") (pinfunction "LC2_LC2") (pintype "bidirectional"))
    )
    (net (code "71") (name "unconnected-(B3-PadL3)") (class "Default")
      (node (ref "B3") (pin "L3") (pinfunction "L3_L3") (pintype "bidirectional"))
    )
    (net (code "72") (name "unconnected-(B3-PadL4)") (class "Default")
      (node (ref "B3") (pin "L4") (pinfunction "L4_L4") (pintype "bidirectional"))
    )
    (net (code "73") (name "unconnected-(B3-PadLC2)") (class "Default")
      (node (ref "B3") (pin "LC2") (pinfunction "LC2_LC2") (pintype "bidirectional"))
    )
    (net (code "74") (name "unconnected-(B4-PadL3)") (class "Default")
      (node (ref "B4") (pin "L3") (pinfunction "L3_L3") (pintype "bidirectional"))
    )
    (net (code "75") (name "unconnected-(B4-PadL4)") (class "Default")
      (node (ref "B4") (pin "L4") (pinfunction "L4_L4") (pintype "bidirectional"))
    )
    (net (code "76") (name "unconnected-(B4-PadLC2)") (class "Default")
      (node (ref "B4") (pin "LC2") (pinfunction "LC2_LC2") (pintype "bidirectional"))
    )
    (net (code "77") (name "unconnected-(B5-PadL3)") (class "Default")
      (node (ref "B5") (pin "L3") (pinfunction "L3_L3") (pintype "bidirectional"))
    )
    (net (code "78") (name "unconnected-(B5-PadL4)") (class "Default")
      (node (ref "B5") (pin "L4") (pinfunction "L4_L4") (pintype "bidirectional"))
    )
    (net (code "79") (name "unconnected-(B5-PadLC2)") (class "Default")
      (node (ref "B5") (pin "LC2") (pinfunction "LC2_LC2") (pintype "bidirectional"))
    )
    (net (code "80") (name "unconnected-(B6-PadL3)") (class "Default")
      (node (ref "B6") (pin "L3") (pinfunction "L3_L3") (pintype "bidirectional"))
    )
    (net (code "81") (name "unconnected-(B6-PadL4)") (class "Default")
      (node (ref "B6") (pin "L4") (pinfunction "L4_L4") (pintype "bidirectional"))
    )
    (net (code "82") (name "unconnected-(B6-PadLC2)") (class "Default")
      (node (ref "B6") (pin "LC2") (pinfunction "LC2_LC2") (pintype "bidirectional"))
    )
    (net (code "83") (name "unconnected-(B7-PadL3)") (class "Default")
      (node (ref "B7") (pin "L3") (pinfunction "L3_L3") (pintype "bidirectional"))
    )
    (net (code "84") (name "unconnected-(B7-PadL4)") (class "Default")
      (node (ref "B7") (pin "L4") (pinfunction "L4_L4") (pintype "bidirectional"))
    )
    (net (code "85") (name "unconnected-(B7-PadLC2)") (class "Default")
      (node (ref "B7") (pin "LC2") (pinfunction "LC2_LC2") (pintype "bidirectional"))
    )
    (net (code "86") (name "unconnected-(B8-PadL3)") (class "Default")
      (node (ref "B8") (pin "L3") (pinfunction "L3_L3") (pintype "bidirectional"))
    )
    (net (code "87") (name "unconnected-(B8-PadL4)") (class "Default")
      (node (ref "B8") (pin "L4") (pinfunction "L4_L4") (pintype "bidirectional"))
    )
    (net (code "88") (name "unconnected-(B8-PadLC2)") (class "Default")
      (node (ref "B8") (pin "LC2") (pinfunction "LC2_LC2") (pintype "bidirectional"))
    )
    (net (code "89") (name "unconnected-(B9-PadL3)") (class "Default")
      (node (ref "B9") (pin "L3") (pinfunction "L3_L3") (pintype "bidirectional"))
    )
    (net (code "90") (name "unconnected-(B9-PadL4)") (class "Default")
      (node (ref "B9") (pin "L4") (pinfunction "L4_L4") (pintype "bidirectional"))
    )
    (net (code "91") (name "unconnected-(B9-PadLC2)") (class "Default")
      (node (ref "B9") (pin "LC2") (pinfunction "LC2_LC2") (pintype "bidirectional"))
    )
    (net (code "92") (name "unconnected-(B10-PadL3)") (class "Default")
      (node (ref "B10") (pin "L3") (pinfunction "L3_L3") (pintype "bidirectional"))
    )
    (net (code "93") (name "unconnected-(B10-PadL4)") (class "Default")
      (node (ref "B10") (pin "L4") (pinfunction "L4_L4") (pintype "bidirectional"))
    )
    (net (code "94") (name "unconnected-(B10-PadLC2)") (class "Default")
      (node (ref "B10") (pin "LC2") (pinfunction "LC2_LC2") (pintype "bidirectional"))
    )
    (net (code "95") (name "unconnected-(B11-PadL3)") (class "Default")
      (node (ref "B11") (pin "L3") (pinfunction "L3_L3") (pintype "bidirectional"))
    )
    (net (code "96") (name "unconnected-(B11-PadL4)") (class "Default")
      (node (ref "B11") (pin "L4") (pinfunction "L4_L4") (pintype "bidirectional"))
    )
    (net (code "97") (name "unconnected-(B11-PadLC2)") (class "Default")
      (node (ref "B11") (pin "LC2") (pinfunction "LC2_LC2") (pintype "bidirectional"))
    )
    (net (code "98") (name "unconnected-(B12-PadL3)") (class "Default")
      (node (ref "B12") (pin "L3") (pinfunction "L3_L3") (pintype "bidirectional"))
    )
    (net (code "99") (name "unconnected-(B12-PadL4)") (class "Default")
      (node (ref "B12") (pin "L4") (pinfunction "L4_L4") (pintype "bidirectional"))
    )
    (net (code "100") (name "unconnected-(B12-PadLC2)") (class "Default")
      (node (ref "B12") (pin "LC2") (pinfunction "LC2_LC2") (pintype "bidirectional"))
    )
    (net (code "101") (name "unconnected-(B13-PadL3)") (class "Default")
      (node (ref "B13") (pin "L3") (pinfunction "L3_L3") (pintype "bidirectional"))
    )
    (net (code "102") (name "unconnected-(B13-PadL4)") (class "Default")
      (node (ref "B13") (pin "L4") (pinfunction "L4_L4") (pintype "bidirectional"))
    )
    (net (code "103") (name "unconnected-(B13-PadLC2)") (class "Default")
      (node (ref "B13") (pin "LC2") (pinfunction "LC2_LC2") (pintype "bidirectional"))
    )
    (net (code "104") (name "unconnected-(B14-PadL3)") (class "Default")
      (node (ref "B14") (pin "L3") (pinfunction "L3_L3") (pintype "bidirectional"))
    )
    (net (code "105") (name "unconnected-(B14-PadL4)") (class "Default")
      (node (ref "B14") (pin "L4") (pinfunction "L4_L4") (pintype "bidirectional"))
    )
    (net (code "106") (name "unconnected-(B14-PadLC2)") (class "Default")
      (node (ref "B14") (pin "LC2") (pinfunction "LC2_LC2") (pintype "bidirectional"))
    )
    (net (code "107") (name "unconnected-(B15-PadL3)") (class "Default")
      (node (ref "B15") (pin "L3") (pinfunction "L3_L3") (pintype "bidirectional"))
    )
    (net (code "108") (name "unconnected-(B15-PadL4)") (class "Default")
      (node (ref "B15") (pin "L4") (pinfunction "L4_L4") (pintype "bidirectional"))
    )
    (net (code "109") (name "unconnected-(B15-PadLC2)") (class "Default")
      (node (ref "B15") (pin "LC2") (pinfunction "LC2_LC2") (pintype "bidirectional"))
    )
    (net (code "110") (name "unconnected-(B16-PadL3)") (class "Default")
      (node (ref "B16") (pin "L3") (pinfunction "L3_L3") (pintype "bidirectional"))
    )
    (net (code "111") (name "unconnected-(B16-PadL4)") (class "Default")
      (node (ref "B16") (pin "L4") (pinfunction "L4_L4") (pintype "bidirectional"))
    )
    (net (code "112") (name "unconnected-(B16-PadLC2)") (class "Default")
      (node (ref "B16") (pin "LC2") (pinfunction "LC2_LC2") (pintype "bidirectional"))
    )
    (net (code "113") (name "unconnected-(GND-*D5-PadD5)") (class "Default")
      (node (ref "GND") (pin "D5") (pinfunction "*D5_D5") (pintype "bidirectional"))
    )
    (net (code "114") (name "unconnected-(GND-*D6-PadD6)") (class "Default")
      (node (ref "GND") (pin "D6") (pinfunction "*D6_D6") (pintype "bidirectional"))
    )
    (net (code "115") (name "unconnected-(GND-*D9-PadD9)") (class "Default")
      (node (ref "GND") (pin "D9") (pinfunction "*D9_D9") (pintype "bidirectional"))
    )
    (net (code "116") (name "unconnected-(GND-*D10-PadD10)") (class "Default")
      (node (ref "GND") (pin "D10") (pinfunction "*D10_D10") (pintype "bidirectional"))
    )
    (net (code "117") (name "unconnected-(GND-*D11-PadD11)") (class "Default")
      (node (ref "GND") (pin "D11") (pinfunction "*D11_D11") (pintype "bidirectional"))
    )
    (net (code "118") (name "unconnected-(GND-Pad3.3V)") (class "Default")
      (node (ref "GND") (pin "3.3V") (pinfunction "3.3V_3.3V") (pintype "bidirectional"))
    )
    (net (code "119") (name "unconnected-(GND-PadA2)") (class "Default")
      (node (ref "GND") (pin "A2") (pinfunction "A2_A2") (pintype "bidirectional"))
    )
    (net (code "120") (name "unconnected-(GND-PadA3)") (class "Default")
      (node (ref "GND") (pin "A3") (pinfunction "A3_A3") (pintype "bidirectional"))
    )
    (net (code "121") (name "unconnected-(GND-PadA4)") (class "Default")
      (node (ref "GND") (pin "A4") (pinfunction "A4_A4") (pintype "bidirectional"))
    )
    (net (code "122") (name "unconnected-(GND-PadA5)") (class "Default")
      (node (ref "GND") (pin "A5") (pinfunction "A5_A5") (pintype "bidirectional"))
    )
    (net (code "123") (name "unconnected-(GND-PadAREF)") (class "Default")
      (node (ref "GND") (pin "AREF") (pinfunction "AREF_AREF") (pintype "bidirectional"))
    )
    (net (code "124") (name "unconnected-(GND-PadD4)") (class "Default")
      (node (ref "GND") (pin "D4") (pinfunction "D4_D4") (pintype "bidirectional"))
    )
    (net (code "125") (name "unconnected-(GND-PadD8)") (class "Default")
      (node (ref "GND") (pin "D8") (pinfunction "D8_D8") (pintype "bidirectional"))
    )
    (net (code "126") (name "unconnected-(GND-PadD12)") (class "Default")
      (node (ref "GND") (pin "D12") (pinfunction "D12_D12") (pintype "bidirectional"))
    )
    (net (code "127") (name "unconnected-(GND-PadD13)") (class "Default")
      (node (ref "GND") (pin "D13") (pinfunction "D13_D13") (pintype "bidirectional"))
    )
    (net (code "128") (name "unconnected-(GND-PadRX)") (class "Default")
      (node (ref "GND") (pin "RX") (pinfunction "RX_RX") (pintype "bidirectional"))
    )
    (net (code "129") (name "unconnected-(GND-PadTX)") (class "Default")
      (node (ref "GND") (pin "TX") (pinfunction "TX_TX") (pintype "bidirectional"))
    )
    (net (code "130") (name "unconnected-(IC4-INTA-Pad20)") (class "Default")
      (node (ref "IC4") (pin "20") (pinfunction "INTA_20") (pintype "output"))
    )
    (net (code "131") (name "unconnected-(IC4-INTB-Pad19)") (class "Default")
      (node (ref "IC4") (pin "19") (pinfunction "INTB_19") (pintype "output"))
    )
    (net (code "132") (name "unconnected-(JP1-Pad1)") (class "Default")
      (node (ref "JP1") (pin "1") (pinfunction "1_1") (pintype "passive"))
    )
    (net (code "133") (name "unconnected-(JP1-Pad2)") (class "Default")
      (node (ref "JP1") (pin "2") (pinfunction "2_2") (pintype "passive"))
    )
  )
)
